# Motor_Surucu.net
KiCad netlist of a schematic drawn in EAGLE
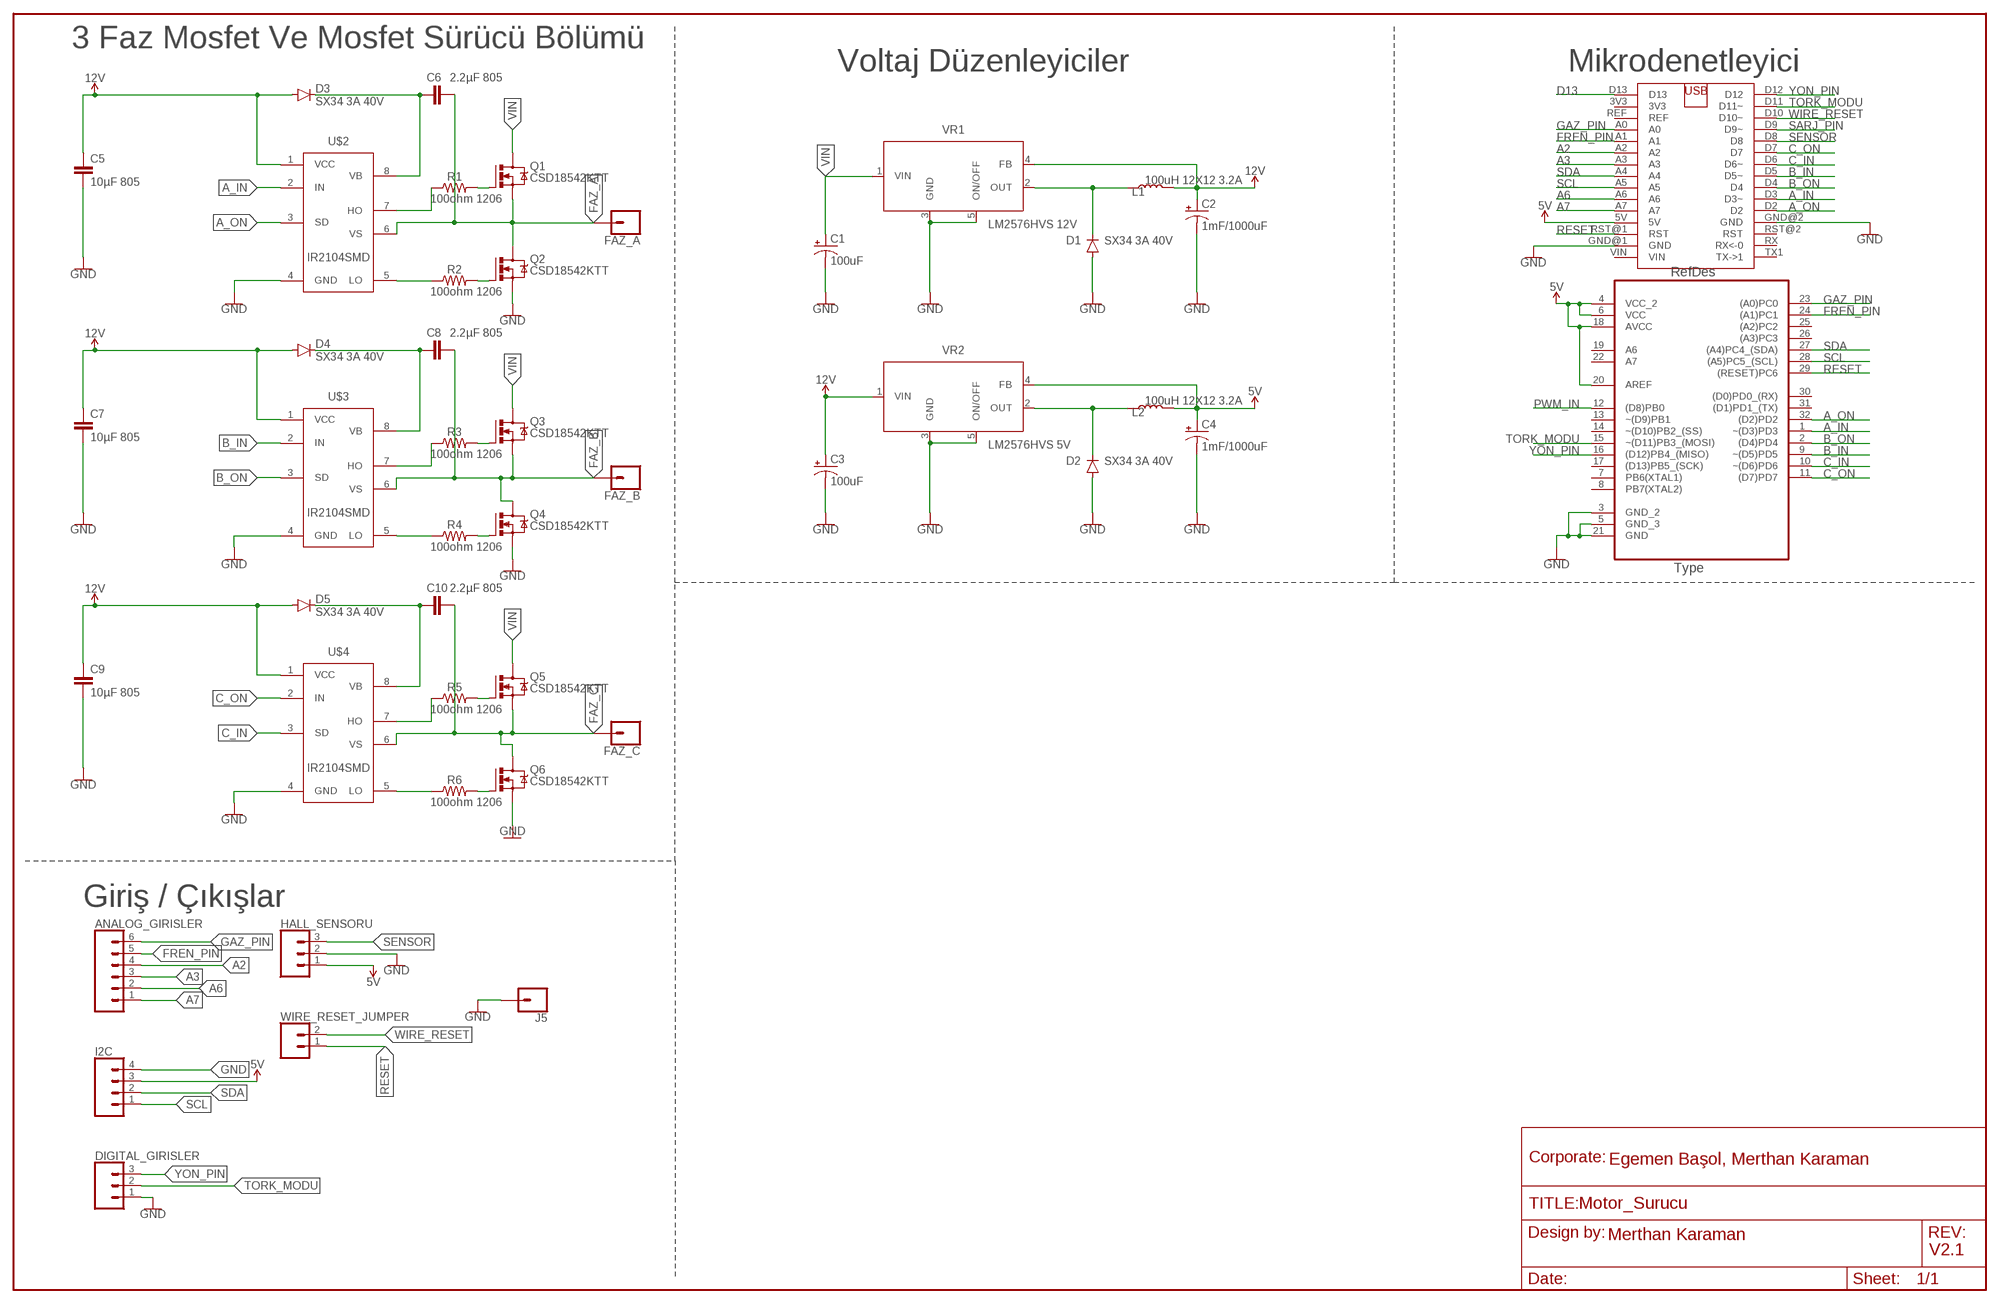
[diagram p0: schematic, sheet 1]

(export (version "E")
  (design (tool "Eeschema 10.0.6"))
  (components
    (comp (ref "ANALOG_GIRISLER")
      (value "CONN_06LOCK")
      (footprint "eagle-import:1X06_LOCK")
      (libsource (lib "eagle-import") (part "CONN_06LOCK"))
    )
    (comp (ref "C1")
      (value "100uF")
      (footprint "eagle-import:CPOL-RADIAL-2.5MM-6.5MM")
      (libsource (lib "eagle-import") (part "100UF-POLAR-RADIAL-2.5MM-25V-20%"))
    )
    (comp (ref "C2")
      (value "1mF/1000uF")
      (footprint "eagle-import:PANASONIC_G")
      (libsource (lib "eagle-import") (part "560UF-PANASONIC_G-25V-20%"))
    )
    (comp (ref "C3")
      (value "100uF")
      (footprint "eagle-import:CPOL-RADIAL-2.5MM-6.5MM")
      (libsource (lib "eagle-import") (part "100UF-POLAR-RADIAL-2.5MM-25V-20%"))
    )
    (comp (ref "C4")
      (value "1mF/1000uF")
      (footprint "eagle-import:PANASONIC_G")
      (libsource (lib "eagle-import") (part "560UF-PANASONIC_G-25V-20%"))
    )
    (comp (ref "C5")
      (value "10µF 805")
      (footprint "eagle-import:0805")
      (libsource (lib "eagle-import") (part "0.33UF/330NF-0805-50V-10%"))
    )
    (comp (ref "C6")
      (value "2.2µF 805")
      (footprint "eagle-import:0805")
      (libsource (lib "eagle-import") (part "0.33UF/330NF-0805-50V-10%"))
    )
    (comp (ref "C7")
      (value "10µF 805")
      (footprint "eagle-import:0805")
      (libsource (lib "eagle-import") (part "0.33UF/330NF-0805-50V-10%"))
    )
    (comp (ref "C8")
      (value "2.2µF 805")
      (footprint "eagle-import:0805")
      (libsource (lib "eagle-import") (part "0.33UF/330NF-0805-50V-10%"))
    )
    (comp (ref "C9")
      (value "10µF 805")
      (footprint "eagle-import:0805")
      (libsource (lib "eagle-import") (part "0.33UF/330NF-0805-50V-10%"))
    )
    (comp (ref "C10")
      (value "2.2µF 805")
      (footprint "eagle-import:0805")
      (libsource (lib "eagle-import") (part "0.33UF/330NF-0805-50V-10%"))
    )
    (comp (ref "D1")
      (value "SX34 3A 40V")
      (footprint "eagle-import:DO214AC")
      (libsource (lib "eagle-import") (part "DIODE-DO214AC"))
    )
    (comp (ref "D2")
      (value "SX34 3A 40V")
      (footprint "eagle-import:DO214AC")
      (libsource (lib "eagle-import") (part "DIODE-DO214AC"))
    )
    (comp (ref "D3")
      (value "SX34 3A 40V")
      (footprint "eagle-import:DO214AC")
      (libsource (lib "eagle-import") (part "DIODE-DO214AC"))
    )
    (comp (ref "D4")
      (value "SX34 3A 40V")
      (footprint "eagle-import:DO214AC")
      (libsource (lib "eagle-import") (part "DIODE-DO214AC"))
    )
    (comp (ref "D5")
      (value "SX34 3A 40V")
      (footprint "eagle-import:DO214AC")
      (libsource (lib "eagle-import") (part "DIODE-DO214AC"))
    )
    (comp (ref "DIGITAL_GIRISLER")
      (value "CONN_03")
      (footprint "eagle-import:1X03")
      (libsource (lib "eagle-import") (part "CONN_03"))
    )
    (comp (ref "FAZ_A")
      (value "CONN_01SNAP-MALE")
      (footprint "eagle-import:SNAP-MALE")
      (libsource (lib "eagle-import") (part "CONN_01SNAP-MALE"))
    )
    (comp (ref "FAZ_B")
      (value "CONN_01SNAP-MALE")
      (footprint "eagle-import:SNAP-MALE")
      (libsource (lib "eagle-import") (part "CONN_01SNAP-MALE"))
    )
    (comp (ref "FAZ_C")
      (value "CONN_01SNAP-MALE")
      (footprint "eagle-import:SNAP-MALE")
      (libsource (lib "eagle-import") (part "CONN_01SNAP-MALE"))
    )
    (comp (ref "HALL_SENSORU")
      (value "CONN_03")
      (footprint "eagle-import:1X03")
      (libsource (lib "eagle-import") (part "CONN_03"))
    )
    (comp (ref "I2C")
      (value "CONN_04")
      (footprint "eagle-import:1X04")
      (libsource (lib "eagle-import") (part "CONN_04"))
    )
    (comp (ref "J5")
      (value "CONN_01SNAP-MALE")
      (footprint "eagle-import:SNAP-MALE")
      (libsource (lib "eagle-import") (part "CONN_01SNAP-MALE"))
    )
    (comp (ref "L1")
      (value "100uH 12X12 3.2A")
      (footprint "eagle-import:INDUCTOR_SDR1307")
      (libsource (lib "eagle-import") (part "INDUCTOR-SDR13-27UH"))
    )
    (comp (ref "L2")
      (value "100uH 12X12 3.2A")
      (footprint "eagle-import:INDUCTOR_SDR1307")
      (libsource (lib "eagle-import") (part "INDUCTOR-SDR13-27UH"))
    )
    (comp (ref "Q1")
      (value "CSD18542KTT")
      (footprint "eagle-import:TO263-3")
      (libsource (lib "eagle-import") (part "CSD18542KTT"))
    )
    (comp (ref "Q2")
      (value "CSD18542KTT")
      (footprint "eagle-import:TO263-3")
      (libsource (lib "eagle-import") (part "CSD18542KTT"))
    )
    (comp (ref "Q3")
      (value "CSD18542KTT")
      (footprint "eagle-import:TO263-3")
      (libsource (lib "eagle-import") (part "CSD18542KTT"))
    )
    (comp (ref "Q4")
      (value "CSD18542KTT")
      (footprint "eagle-import:TO263-3")
      (libsource (lib "eagle-import") (part "CSD18542KTT"))
    )
    (comp (ref "Q5")
      (value "CSD18542KTT")
      (footprint "eagle-import:TO263-3")
      (libsource (lib "eagle-import") (part "CSD18542KTT"))
    )
    (comp (ref "Q6")
      (value "CSD18542KTT")
      (footprint "eagle-import:TO263-3")
      (libsource (lib "eagle-import") (part "CSD18542KTT"))
    )
    (comp (ref "R1")
      (value "100ohm 1206")
      (footprint "eagle-import:1206")
      (libsource (lib "eagle-import") (part "RESISTOR1206"))
    )
    (comp (ref "R2")
      (value "100ohm 1206")
      (footprint "eagle-import:1206")
      (libsource (lib "eagle-import") (part "RESISTOR1206"))
    )
    (comp (ref "R3")
      (value "100ohm 1206")
      (footprint "eagle-import:1206")
      (libsource (lib "eagle-import") (part "RESISTOR1206"))
    )
    (comp (ref "R4")
      (value "100ohm 1206")
      (footprint "eagle-import:1206")
      (libsource (lib "eagle-import") (part "RESISTOR1206"))
    )
    (comp (ref "R5")
      (value "100ohm 1206")
      (footprint "eagle-import:1206")
      (libsource (lib "eagle-import") (part "RESISTOR1206"))
    )
    (comp (ref "R6")
      (value "100ohm 1206")
      (footprint "eagle-import:1206")
      (libsource (lib "eagle-import") (part "RESISTOR1206"))
    )
    (comp (ref "U$1")
      (value "ARDUINO_NANO")
      (footprint "eagle-import:ARDUINO_NANO")
      (libsource (lib "eagle-import") (part "ARDUINO_NANO"))
    )
    (comp (ref "U$2")
      (value "IR2104SMD")
      (footprint "eagle-import:SOIC-8")
      (libsource (lib "eagle-import") (part "IR2104SMD"))
    )
    (comp (ref "U$3")
      (value "IR2104SMD")
      (footprint "eagle-import:SOIC-8")
      (libsource (lib "eagle-import") (part "IR2104SMD"))
    )
    (comp (ref "U$4")
      (value "IR2104SMD")
      (footprint "eagle-import:SOIC-8")
      (libsource (lib "eagle-import") (part "IR2104SMD"))
    )
    (comp (ref "U1")
      (value "ATMEGA328P-AU")
      (footprint "eagle-import:QFP80P900X900X120-32N")
      (libsource (lib "eagle-import") (part "ATMEGA328P-AU"))
    )
    (comp (ref "VR1")
      (value "LM2576HVS 12V")
      (footprint "eagle-import:TO170P1435X465-6N")
      (fields (field (name "MANUFACTURER") "TI") (field (name "MPN") "LM2576HVS-5.0/NOPB"))
      (libsource (lib "eagle-import") (part "LM2576HVS-5.0/NOPBTO-263"))
    )
    (comp (ref "VR2")
      (value "LM2576HVS 5V")
      (footprint "eagle-import:TO170P1435X465-6N")
      (fields (field (name "MANUFACTURER") "TI") (field (name "MPN") "LM2576HVS-5.0/NOPB"))
      (libsource (lib "eagle-import") (part "LM2576HVS-5.0/NOPBTO-263"))
    )
    (comp (ref "WIRE_RESET_JUMPER")
      (value "CONN_02")
      (footprint "eagle-import:1X02")
      (libsource (lib "eagle-import") (part "CONN_02"))
    )
  )
  (nets
    (net (code "1") (name "/D13") (class "Default")
      (node (ref "U$1") (pin "D13") (pinfunction "D13_D13") (pintype "bidirectional"))
    )
    (net (code "2") (name "/PWM_IN") (class "Default")
      (node (ref "U1") (pin "12") (pinfunction "(D8)PB0_12") (pintype "bidirectional"))
    )
    (net (code "3") (name "/SARJ_PIN") (class "Default")
      (node (ref "U$1") (pin "D9") (pinfunction "D9~{}_D9") (pintype "bidirectional"))
    )
    (net (code "4") (name "5V") (class "Default")
      (node (ref "C4") (pin "+") (pinfunction "+_+") (pintype "passive"))
      (node (ref "HALL_SENSORU") (pin "1") (pinfunction "1_1") (pintype "passive"))
      (node (ref "I2C") (pin "3") (pinfunction "3_3") (pintype "passive"))
      (node (ref "L2") (pin "P$2") (pinfunction "2_P$2") (pintype "passive"))
      (node (ref "U$1") (pin "5V") (pinfunction "5V_5V") (pintype "bidirectional"))
      (node (ref "U1") (pin "18") (pinfunction "AVCC_18") (pintype "power_in"))
      (node (ref "U1") (pin "20") (pinfunction "AREF_20") (pintype "input"))
      (node (ref "U1") (pin "4") (pinfunction "VCC_2_4") (pintype "power_in"))
      (node (ref "U1") (pin "6") (pinfunction "VCC_6") (pintype "power_in"))
      (node (ref "VR2") (pin "4") (pinfunction "FB_4") (pintype "output"))
    )
    (net (code "5") (name "12V") (class "Default")
      (node (ref "C2") (pin "+") (pinfunction "+_+") (pintype "passive"))
      (node (ref "C3") (pin "1") (pinfunction "+_1") (pintype "passive"))
      (node (ref "C5") (pin "1") (pinfunction "1_1") (pintype "passive"))
      (node (ref "C7") (pin "1") (pinfunction "1_1") (pintype "passive"))
      (node (ref "C9") (pin "1") (pinfunction "1_1") (pintype "passive"))
      (node (ref "D3") (pin "A") (pinfunction "A_A") (pintype "passive"))
      (node (ref "D4") (pin "A") (pinfunction "A_A") (pintype "passive"))
      (node (ref "D5") (pin "A") (pinfunction "A_A") (pintype "passive"))
      (node (ref "L1") (pin "P$2") (pinfunction "2_P$2") (pintype "passive"))
      (node (ref "U$2") (pin "1") (pinfunction "VCC_1") (pintype "bidirectional"))
      (node (ref "U$3") (pin "1") (pinfunction "VCC_1") (pintype "bidirectional"))
      (node (ref "U$4") (pin "1") (pinfunction "VCC_1") (pintype "bidirectional"))
      (node (ref "VR1") (pin "4") (pinfunction "FB_4") (pintype "output"))
      (node (ref "VR2") (pin "1") (pinfunction "VIN_1") (pintype "input"))
    )
    (net (code "6") (name "A2") (class "Default")
      (node (ref "ANALOG_GIRISLER") (pin "4") (pinfunction "4_4") (pintype "passive"))
      (node (ref "U$1") (pin "A2") (pinfunction "A2_A2") (pintype "bidirectional"))
    )
    (net (code "7") (name "A3") (class "Default")
      (node (ref "ANALOG_GIRISLER") (pin "3") (pinfunction "3_3") (pintype "passive"))
      (node (ref "U$1") (pin "A3") (pinfunction "A3_A3") (pintype "bidirectional"))
    )
    (net (code "8") (name "A6") (class "Default")
      (node (ref "ANALOG_GIRISLER") (pin "2") (pinfunction "2_2") (pintype "passive"))
      (node (ref "U$1") (pin "A6") (pinfunction "A6_A6") (pintype "bidirectional"))
    )
    (net (code "9") (name "A7") (class "Default")
      (node (ref "ANALOG_GIRISLER") (pin "1") (pinfunction "1_1") (pintype "passive"))
      (node (ref "U$1") (pin "A7") (pinfunction "A7_A7") (pintype "bidirectional"))
    )
    (net (code "10") (name "A_IN") (class "Default")
      (node (ref "U$1") (pin "D3") (pinfunction "D3~{}_D3") (pintype "bidirectional"))
      (node (ref "U$2") (pin "2") (pinfunction "IN_2") (pintype "bidirectional"))
      (node (ref "U1") (pin "1") (pinfunction "~{(D3})PD3_1") (pintype "bidirectional"))
    )
    (net (code "11") (name "A_ON") (class "Default")
      (node (ref "U$1") (pin "D2") (pinfunction "D2_D2") (pintype "bidirectional"))
      (node (ref "U$2") (pin "3") (pinfunction "SD_3") (pintype "bidirectional"))
      (node (ref "U1") (pin "32") (pinfunction "(D2)PD2_32") (pintype "bidirectional"))
    )
    (net (code "12") (name "B_IN") (class "Default")
      (node (ref "U$1") (pin "D5") (pinfunction "D5~{}_D5") (pintype "bidirectional"))
      (node (ref "U$3") (pin "2") (pinfunction "IN_2") (pintype "bidirectional"))
      (node (ref "U1") (pin "9") (pinfunction "~{(D5})PD5_9") (pintype "bidirectional"))
    )
    (net (code "13") (name "B_ON") (class "Default")
      (node (ref "U$1") (pin "D4") (pinfunction "D4_D4") (pintype "bidirectional"))
      (node (ref "U$3") (pin "3") (pinfunction "SD_3") (pintype "bidirectional"))
      (node (ref "U1") (pin "2") (pinfunction "(D4)PD4_2") (pintype "bidirectional"))
    )
    (net (code "14") (name "C_IN") (class "Default")
      (node (ref "U$1") (pin "D6") (pinfunction "D6~{}_D6") (pintype "bidirectional"))
      (node (ref "U$4") (pin "3") (pinfunction "SD_3") (pintype "bidirectional"))
      (node (ref "U1") (pin "10") (pinfunction "~{(D6})PD6_10") (pintype "bidirectional"))
    )
    (net (code "15") (name "C_ON") (class "Default")
      (node (ref "U$1") (pin "D7") (pinfunction "D7_D7") (pintype "bidirectional"))
      (node (ref "U$4") (pin "2") (pinfunction "IN_2") (pintype "bidirectional"))
      (node (ref "U1") (pin "11") (pinfunction "(D7)PD7_11") (pintype "bidirectional"))
    )
    (net (code "16") (name "FAZ_A") (class "Default")
      (node (ref "C6") (pin "2") (pinfunction "2_2") (pintype "passive"))
      (node (ref "FAZ_A") (pin "2") (pinfunction "1_2") (pintype "passive"))
      (node (ref "Q1") (pin "3") (pinfunction "S_3") (pintype "passive"))
      (node (ref "Q2") (pin "TAB") (pinfunction "D_TAB") (pintype "passive"))
      (node (ref "U$2") (pin "6") (pinfunction "VS_6") (pintype "bidirectional"))
    )
    (net (code "17") (name "FAZ_B") (class "Default")
      (node (ref "C8") (pin "2") (pinfunction "2_2") (pintype "passive"))
      (node (ref "FAZ_B") (pin "2") (pinfunction "1_2") (pintype "passive"))
      (node (ref "Q3") (pin "3") (pinfunction "S_3") (pintype "passive"))
      (node (ref "Q4") (pin "TAB") (pinfunction "D_TAB") (pintype "passive"))
      (node (ref "U$3") (pin "6") (pinfunction "VS_6") (pintype "bidirectional"))
    )
    (net (code "18") (name "FAZ_C") (class "Default")
      (node (ref "C10") (pin "2") (pinfunction "2_2") (pintype "passive"))
      (node (ref "FAZ_C") (pin "2") (pinfunction "1_2") (pintype "passive"))
      (node (ref "Q5") (pin "3") (pinfunction "S_3") (pintype "passive"))
      (node (ref "Q6") (pin "TAB") (pinfunction "D_TAB") (pintype "passive"))
      (node (ref "U$4") (pin "6") (pinfunction "VS_6") (pintype "bidirectional"))
    )
    (net (code "19") (name "FREN_PIN") (class "Default")
      (node (ref "ANALOG_GIRISLER") (pin "5") (pinfunction "5_5") (pintype "passive"))
      (node (ref "U$1") (pin "A1") (pinfunction "A1_A1") (pintype "bidirectional"))
      (node (ref "U1") (pin "24") (pinfunction "(A1)PC1_24") (pintype "bidirectional"))
    )
    (net (code "20") (name "GAZ_PIN") (class "Default")
      (node (ref "ANALOG_GIRISLER") (pin "6") (pinfunction "6_6") (pintype "passive"))
      (node (ref "U$1") (pin "A0") (pinfunction "A0_A0") (pintype "bidirectional"))
      (node (ref "U1") (pin "23") (pinfunction "(A0)PC0_23") (pintype "bidirectional"))
    )
    (net (code "21") (name "GND") (class "Default")
      (node (ref "C1") (pin "2") (pinfunction "-_2") (pintype "passive"))
      (node (ref "C2") (pin "-") (pinfunction "-_-") (pintype "passive"))
      (node (ref "C3") (pin "2") (pinfunction "-_2") (pintype "passive"))
      (node (ref "C4") (pin "-") (pinfunction "-_-") (pintype "passive"))
      (node (ref "C5") (pin "2") (pinfunction "2_2") (pintype "passive"))
      (node (ref "C7") (pin "2") (pinfunction "2_2") (pintype "passive"))
      (node (ref "C9") (pin "2") (pinfunction "2_2") (pintype "passive"))
      (node (ref "D1") (pin "A") (pinfunction "A_A") (pintype "passive"))
      (node (ref "D2") (pin "A") (pinfunction "A_A") (pintype "passive"))
      (node (ref "DIGITAL_GIRISLER") (pin "1") (pinfunction "1_1") (pintype "passive"))
      (node (ref "HALL_SENSORU") (pin "2") (pinfunction "2_2") (pintype "passive"))
      (node (ref "I2C") (pin "4") (pinfunction "4_4") (pintype "passive"))
      (node (ref "J5") (pin "2") (pinfunction "1_2") (pintype "passive"))
      (node (ref "Q2") (pin "3") (pinfunction "S_3") (pintype "passive"))
      (node (ref "Q4") (pin "3") (pinfunction "S_3") (pintype "passive"))
      (node (ref "Q6") (pin "3") (pinfunction "S_3") (pintype "passive"))
      (node (ref "U$1") (pin "GND@1") (pinfunction "GND_GND@1") (pintype "bidirectional"))
      (node (ref "U$1") (pin "GND@2") (pinfunction "GND_GND@2") (pintype "bidirectional"))
      (node (ref "U$2") (pin "4") (pinfunction "GND_4") (pintype "bidirectional"))
      (node (ref "U$3") (pin "4") (pinfunction "GND_4") (pintype "bidirectional"))
      (node (ref "U$4") (pin "4") (pinfunction "GND_4") (pintype "bidirectional"))
      (node (ref "U1") (pin "21") (pinfunction "GND_21") (pintype "passive"))
      (node (ref "U1") (pin "3") (pinfunction "GND_2_3") (pintype "passive"))
      (node (ref "U1") (pin "5") (pinfunction "GND_3_5") (pintype "passive"))
      (node (ref "VR1") (pin "3") (pinfunction "GND_3") (pintype "passive"))
      (node (ref "VR1") (pin "5") (pinfunction "ON/OFF_5") (pintype "input"))
      (node (ref "VR2") (pin "3") (pinfunction "GND_3") (pintype "passive"))
      (node (ref "VR2") (pin "5") (pinfunction "ON/OFF_5") (pintype "input"))
    )
    (net (code "22") (name "Net-(L1-1)") (class "Default")
      (node (ref "D1") (pin "C") (pinfunction "C_C") (pintype "passive"))
      (node (ref "L1") (pin "P$1") (pinfunction "1_P$1") (pintype "passive"))
      (node (ref "VR1") (pin "2") (pinfunction "OUT_2") (pintype "output"))
    )
    (net (code "23") (name "Net-(L2-1)") (class "Default")
      (node (ref "D2") (pin "C") (pinfunction "C_C") (pintype "passive"))
      (node (ref "L2") (pin "P$1") (pinfunction "1_P$1") (pintype "passive"))
      (node (ref "VR2") (pin "2") (pinfunction "OUT_2") (pintype "output"))
    )
    (net (code "24") (name "Net-(Q1-G)") (class "Default")
      (node (ref "Q1") (pin "1") (pinfunction "G_1") (pintype "passive"))
      (node (ref "R1") (pin "2") (pinfunction "2_2") (pintype "passive"))
    )
    (net (code "25") (name "Net-(Q2-G)") (class "Default")
      (node (ref "Q2") (pin "1") (pinfunction "G_1") (pintype "passive"))
      (node (ref "R2") (pin "2") (pinfunction "2_2") (pintype "passive"))
    )
    (net (code "26") (name "Net-(Q3-G)") (class "Default")
      (node (ref "Q3") (pin "1") (pinfunction "G_1") (pintype "passive"))
      (node (ref "R3") (pin "2") (pinfunction "2_2") (pintype "passive"))
    )
    (net (code "27") (name "Net-(Q4-G)") (class "Default")
      (node (ref "Q4") (pin "1") (pinfunction "G_1") (pintype "passive"))
      (node (ref "R4") (pin "2") (pinfunction "2_2") (pintype "passive"))
    )
    (net (code "28") (name "Net-(Q5-G)") (class "Default")
      (node (ref "Q5") (pin "1") (pinfunction "G_1") (pintype "passive"))
      (node (ref "R5") (pin "2") (pinfunction "2_2") (pintype "passive"))
    )
    (net (code "29") (name "Net-(Q6-G)") (class "Default")
      (node (ref "Q6") (pin "1") (pinfunction "G_1") (pintype "passive"))
      (node (ref "R6") (pin "2") (pinfunction "2_2") (pintype "passive"))
    )
    (net (code "30") (name "Net-(U$2-HO)") (class "Default")
      (node (ref "R1") (pin "1") (pinfunction "1_1") (pintype "passive"))
      (node (ref "U$2") (pin "7") (pinfunction "HO_7") (pintype "bidirectional"))
    )
    (net (code "31") (name "Net-(U$2-LO)") (class "Default")
      (node (ref "R2") (pin "1") (pinfunction "1_1") (pintype "passive"))
      (node (ref "U$2") (pin "5") (pinfunction "LO_5") (pintype "bidirectional"))
    )
    (net (code "32") (name "Net-(U$2-VB)") (class "Default")
      (node (ref "C6") (pin "1") (pinfunction "1_1") (pintype "passive"))
      (node (ref "D3") (pin "C") (pinfunction "C_C") (pintype "passive"))
      (node (ref "U$2") (pin "8") (pinfunction "VB_8") (pintype "bidirectional"))
    )
    (net (code "33") (name "Net-(U$3-HO)") (class "Default")
      (node (ref "R3") (pin "1") (pinfunction "1_1") (pintype "passive"))
      (node (ref "U$3") (pin "7") (pinfunction "HO_7") (pintype "bidirectional"))
    )
    (net (code "34") (name "Net-(U$3-LO)") (class "Default")
      (node (ref "R4") (pin "1") (pinfunction "1_1") (pintype "passive"))
      (node (ref "U$3") (pin "5") (pinfunction "LO_5") (pintype "bidirectional"))
    )
    (net (code "35") (name "Net-(U$3-VB)") (class "Default")
      (node (ref "C8") (pin "1") (pinfunction "1_1") (pintype "passive"))
      (node (ref "D4") (pin "C") (pinfunction "C_C") (pintype "passive"))
      (node (ref "U$3") (pin "8") (pinfunction "VB_8") (pintype "bidirectional"))
    )
    (net (code "36") (name "Net-(U$4-HO)") (class "Default")
      (node (ref "R5") (pin "1") (pinfunction "1_1") (pintype "passive"))
      (node (ref "U$4") (pin "7") (pinfunction "HO_7") (pintype "bidirectional"))
    )
    (net (code "37") (name "Net-(U$4-LO)") (class "Default")
      (node (ref "R6") (pin "1") (pinfunction "1_1") (pintype "passive"))
      (node (ref "U$4") (pin "5") (pinfunction "LO_5") (pintype "bidirectional"))
    )
    (net (code "38") (name "Net-(U$4-VB)") (class "Default")
      (node (ref "C10") (pin "1") (pinfunction "1_1") (pintype "passive"))
      (node (ref "D5") (pin "C") (pinfunction "C_C") (pintype "passive"))
      (node (ref "U$4") (pin "8") (pinfunction "VB_8") (pintype "bidirectional"))
    )
    (net (code "39") (name "RESET") (class "Default")
      (node (ref "U$1") (pin "RST@1") (pinfunction "RST_RST@1") (pintype "bidirectional"))
      (node (ref "U1") (pin "29") (pinfunction "(RESET)PC6_29") (pintype "bidirectional"))
      (node (ref "WIRE_RESET_JUMPER") (pin "1") (pinfunction "1_1") (pintype "passive"))
    )
    (net (code "40") (name "SCL") (class "Default")
      (node (ref "I2C") (pin "1") (pinfunction "1_1") (pintype "passive"))
      (node (ref "U$1") (pin "A5") (pinfunction "A5_A5") (pintype "bidirectional"))
      (node (ref "U1") (pin "28") (pinfunction "(A5)PC5_(SCL)_28") (pintype "bidirectional"))
    )
    (net (code "41") (name "SDA") (class "Default")
      (node (ref "I2C") (pin "2") (pinfunction "2_2") (pintype "passive"))
      (node (ref "U$1") (pin "A4") (pinfunction "A4_A4") (pintype "bidirectional"))
      (node (ref "U1") (pin "27") (pinfunction "(A4)PC4_(SDA)_27") (pintype "bidirectional"))
    )
    (net (code "42") (name "SENSOR") (class "Default")
      (node (ref "HALL_SENSORU") (pin "3") (pinfunction "3_3") (pintype "passive"))
      (node (ref "U$1") (pin "D8") (pinfunction "D8_D8") (pintype "bidirectional"))
    )
    (net (code "43") (name "TORK_MODU") (class "Default")
      (node (ref "DIGITAL_GIRISLER") (pin "2") (pinfunction "2_2") (pintype "passive"))
      (node (ref "U$1") (pin "D11") (pinfunction "D11~{}_D11") (pintype "bidirectional"))
      (node (ref "U1") (pin "15") (pinfunction "~{(D11})PB3_(MOSI)_15") (pintype "bidirectional"))
    )
    (net (code "44") (name "VIN") (class "Default")
      (node (ref "C1") (pin "1") (pinfunction "+_1") (pintype "passive"))
      (node (ref "Q1") (pin "TAB") (pinfunction "D_TAB") (pintype "passive"))
      (node (ref "Q3") (pin "TAB") (pinfunction "D_TAB") (pintype "passive"))
      (node (ref "Q5") (pin "TAB") (pinfunction "D_TAB") (pintype "passive"))
      (node (ref "VR1") (pin "1") (pinfunction "VIN_1") (pintype "input"))
    )
    (net (code "45") (name "WIRE_RESET") (class "Default")
      (node (ref "U$1") (pin "D10") (pinfunction "D10~{}_D10") (pintype "bidirectional"))
      (node (ref "WIRE_RESET_JUMPER") (pin "2") (pinfunction "2_2") (pintype "passive"))
    )
    (net (code "46") (name "YON_PIN") (class "Default")
      (node (ref "DIGITAL_GIRISLER") (pin "3") (pinfunction "3_3") (pintype "passive"))
      (node (ref "U$1") (pin "D12") (pinfunction "D12_D12") (pintype "bidirectional"))
      (node (ref "U1") (pin "16") (pinfunction "(D12)PB4_(MISO)_16") (pintype "bidirectional"))
    )
    (net (code "47") (name "unconnected-(U$1-Pad3V3)") (class "Default")
      (node (ref "U$1") (pin "3V3") (pinfunction "3V3_3V3") (pintype "bidirectional"))
    )
    (net (code "48") (name "unconnected-(U$1-PadREF)") (class "Default")
      (node (ref "U$1") (pin "REF") (pinfunction "REF_REF") (pintype "bidirectional"))
    )
    (net (code "49") (name "unconnected-(U$1-PadVIN)") (class "Default")
      (node (ref "U$1") (pin "VIN") (pinfunction "VIN_VIN") (pintype "bidirectional"))
    )
    (net (code "50") (name "unconnected-(U$1-RST-PadRST@2)") (class "Default")
      (node (ref "U$1") (pin "RST@2") (pinfunction "RST_RST@2") (pintype "bidirectional"))
    )
    (net (code "51") (name "unconnected-(U$1-RX<-0-PadRX)") (class "Default")
      (node (ref "U$1") (pin "RX") (pinfunction "RX<-0_RX") (pintype "bidirectional"))
    )
    (net (code "52") (name "unconnected-(U$1-TX->1-PadTX1)") (class "Default")
      (node (ref "U$1") (pin "TX1") (pinfunction "TX->1_TX1") (pintype "bidirectional"))
    )
    (net (code "53") (name "unconnected-(U1-(A2)PC2-Pad25)") (class "Default")
      (node (ref "U1") (pin "25") (pinfunction "(A2)PC2_25") (pintype "bidirectional"))
    )
    (net (code "54") (name "unconnected-(U1-(A3)PC3-Pad26)") (class "Default")
      (node (ref "U1") (pin "26") (pinfunction "(A3)PC3_26") (pintype "bidirectional"))
    )
    (net (code "55") (name "unconnected-(U1-(D0)PD0_(RX)-Pad30)") (class "Default")
      (node (ref "U1") (pin "30") (pinfunction "(D0)PD0_(RX)_30") (pintype "bidirectional"))
    )
    (net (code "56") (name "unconnected-(U1-(D1)PD1_(TX)-Pad31)") (class "Default")
      (node (ref "U1") (pin "31") (pinfunction "(D1)PD1_(TX)_31") (pintype "bidirectional"))
    )
    (net (code "57") (name "unconnected-(U1-(D13)PB5_(SCK)-Pad17)") (class "Default")
      (node (ref "U1") (pin "17") (pinfunction "(D13)PB5_(SCK)_17") (pintype "bidirectional"))
    )
    (net (code "58") (name "unconnected-(U1-A6-Pad19)") (class "Default")
      (node (ref "U1") (pin "19") (pinfunction "A6_19") (pintype "input"))
    )
    (net (code "59") (name "unconnected-(U1-A7-Pad22)") (class "Default")
      (node (ref "U1") (pin "22") (pinfunction "A7_22") (pintype "input"))
    )
    (net (code "60") (name "unconnected-(U1-PB6(XTAL1)-Pad7)") (class "Default")
      (node (ref "U1") (pin "7") (pinfunction "PB6(XTAL1)_7") (pintype "bidirectional"))
    )
    (net (code "61") (name "unconnected-(U1-PB7(XTAL2)-Pad8)") (class "Default")
      (node (ref "U1") (pin "8") (pinfunction "PB7(XTAL2)_8") (pintype "bidirectional"))
    )
    (net (code "62") (name "unconnected-(U1-~{(D9})PB1-Pad13)") (class "Default")
      (node (ref "U1") (pin "13") (pinfunction "~{(D9})PB1_13") (pintype "bidirectional"))
    )
    (net (code "63") (name "unconnected-(U1-~{(D10})PB2_(SS)-Pad14)") (class "Default")
      (node (ref "U1") (pin "14") (pinfunction "~{(D10})PB2_(SS)_14") (pintype "bidirectional"))
    )
  )
)
